# sr_indicator_v0_revA.net
KiCad netlist of a schematic drawn in EAGLE
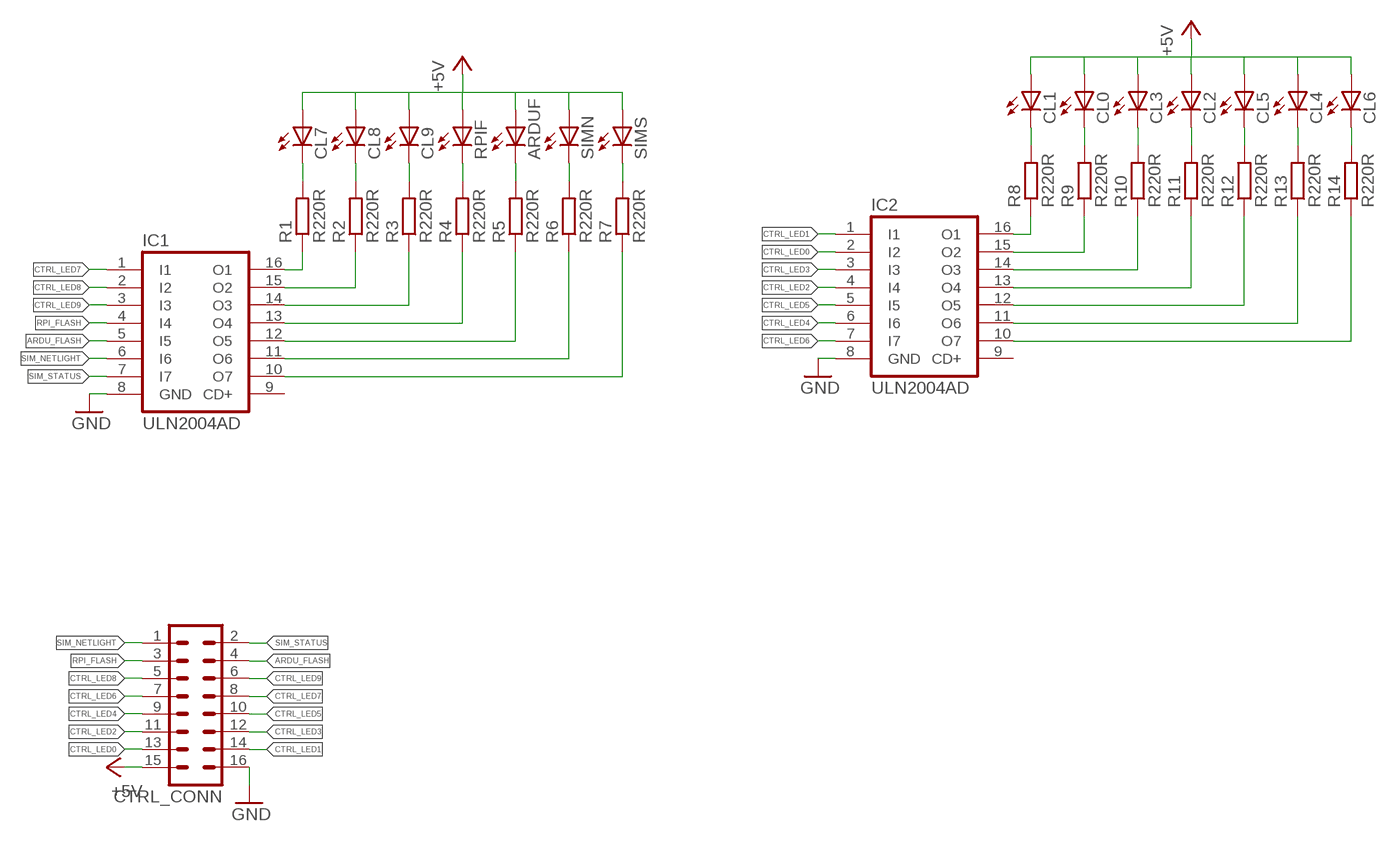
[diagram p0: schematic, sheet 1]

(export (version "E")
  (design (tool "Eeschema 10.0.6"))
  (components
    (comp (ref "ARDUF")
      (value "LED3MM")
      (footprint "eagle-import:LED3MM")
      (libsource (lib "eagle-import") (part "LED3MM"))
    )
    (comp (ref "CL0")
      (value "LED3MM")
      (footprint "eagle-import:LED3MM")
      (libsource (lib "eagle-import") (part "LED3MM"))
    )
    (comp (ref "CL1")
      (value "LED3MM")
      (footprint "eagle-import:LED3MM")
      (libsource (lib "eagle-import") (part "LED3MM"))
    )
    (comp (ref "CL2")
      (value "LED3MM")
      (footprint "eagle-import:LED3MM")
      (libsource (lib "eagle-import") (part "LED3MM"))
    )
    (comp (ref "CL3")
      (value "LED3MM")
      (footprint "eagle-import:LED3MM")
      (libsource (lib "eagle-import") (part "LED3MM"))
    )
    (comp (ref "CL4")
      (value "LED3MM")
      (footprint "eagle-import:LED3MM")
      (libsource (lib "eagle-import") (part "LED3MM"))
    )
    (comp (ref "CL5")
      (value "LED3MM")
      (footprint "eagle-import:LED3MM")
      (libsource (lib "eagle-import") (part "LED3MM"))
    )
    (comp (ref "CL6")
      (value "LED3MM")
      (footprint "eagle-import:LED3MM")
      (libsource (lib "eagle-import") (part "LED3MM"))
    )
    (comp (ref "CL7")
      (value "LED3MM")
      (footprint "eagle-import:LED3MM")
      (libsource (lib "eagle-import") (part "LED3MM"))
    )
    (comp (ref "CL8")
      (value "LED3MM")
      (footprint "eagle-import:LED3MM")
      (libsource (lib "eagle-import") (part "LED3MM"))
    )
    (comp (ref "CL9")
      (value "LED3MM")
      (footprint "eagle-import:LED3MM")
      (libsource (lib "eagle-import") (part "LED3MM"))
    )
    (comp (ref "CTRL_CONN")
      (value "MA08-2")
      (footprint "eagle-import:MA08-2")
      (libsource (lib "eagle-import") (part "MA08-2"))
    )
    (comp (ref "IC1")
      (value "ULN2004AD")
      (footprint "eagle-import:SO16")
      (libsource (lib "eagle-import") (part "ULN2004AD"))
    )
    (comp (ref "IC2")
      (value "ULN2004AD")
      (footprint "eagle-import:SO16")
      (libsource (lib "eagle-import") (part "ULN2004AD"))
    )
    (comp (ref "R1")
      (value "R220R")
      (footprint "eagle-import:M0805")
      (libsource (lib "eagle-import") (part "R-EU_M0805"))
    )
    (comp (ref "R2")
      (value "R220R")
      (footprint "eagle-import:M0805")
      (libsource (lib "eagle-import") (part "R-EU_M0805"))
    )
    (comp (ref "R3")
      (value "R220R")
      (footprint "eagle-import:M0805")
      (libsource (lib "eagle-import") (part "R-EU_M0805"))
    )
    (comp (ref "R4")
      (value "R220R")
      (footprint "eagle-import:M0805")
      (libsource (lib "eagle-import") (part "R-EU_M0805"))
    )
    (comp (ref "R5")
      (value "R220R")
      (footprint "eagle-import:M0805")
      (libsource (lib "eagle-import") (part "R-EU_M0805"))
    )
    (comp (ref "R6")
      (value "R220R")
      (footprint "eagle-import:M0805")
      (libsource (lib "eagle-import") (part "R-EU_M0805"))
    )
    (comp (ref "R7")
      (value "R220R")
      (footprint "eagle-import:M0805")
      (libsource (lib "eagle-import") (part "R-EU_M0805"))
    )
    (comp (ref "R8")
      (value "R220R")
      (footprint "eagle-import:M0805")
      (libsource (lib "eagle-import") (part "R-EU_M0805"))
    )
    (comp (ref "R9")
      (value "R220R")
      (footprint "eagle-import:M0805")
      (libsource (lib "eagle-import") (part "R-EU_M0805"))
    )
    (comp (ref "R10")
      (value "R220R")
      (footprint "eagle-import:M0805")
      (libsource (lib "eagle-import") (part "R-EU_M0805"))
    )
    (comp (ref "R11")
      (value "R220R")
      (footprint "eagle-import:M0805")
      (libsource (lib "eagle-import") (part "R-EU_M0805"))
    )
    (comp (ref "R12")
      (value "R220R")
      (footprint "eagle-import:M0805")
      (libsource (lib "eagle-import") (part "R-EU_M0805"))
    )
    (comp (ref "R13")
      (value "R220R")
      (footprint "eagle-import:M0805")
      (libsource (lib "eagle-import") (part "R-EU_M0805"))
    )
    (comp (ref "R14")
      (value "R220R")
      (footprint "eagle-import:M0805")
      (libsource (lib "eagle-import") (part "R-EU_M0805"))
    )
    (comp (ref "RPIF")
      (value "LED3MM")
      (footprint "eagle-import:LED3MM")
      (libsource (lib "eagle-import") (part "LED3MM"))
    )
    (comp (ref "SIMN")
      (value "LED3MM")
      (footprint "eagle-import:LED3MM")
      (libsource (lib "eagle-import") (part "LED3MM"))
    )
    (comp (ref "SIMS")
      (value "LED3MM")
      (footprint "eagle-import:LED3MM")
      (libsource (lib "eagle-import") (part "LED3MM"))
    )
  )
  (nets
    (net (code "1") (name "+5V") (class "Default")
      (node (ref "ARDUF") (pin "A") (pinfunction "A_A") (pintype "passive"))
      (node (ref "CL0") (pin "A") (pinfunction "A_A") (pintype "passive"))
      (node (ref "CL1") (pin "A") (pinfunction "A_A") (pintype "passive"))
      (node (ref "CL2") (pin "A") (pinfunction "A_A") (pintype "passive"))
      (node (ref "CL3") (pin "A") (pinfunction "A_A") (pintype "passive"))
      (node (ref "CL4") (pin "A") (pinfunction "A_A") (pintype "passive"))
      (node (ref "CL5") (pin "A") (pinfunction "A_A") (pintype "passive"))
      (node (ref "CL6") (pin "A") (pinfunction "A_A") (pintype "passive"))
      (node (ref "CL7") (pin "A") (pinfunction "A_A") (pintype "passive"))
      (node (ref "CL8") (pin "A") (pinfunction "A_A") (pintype "passive"))
      (node (ref "CL9") (pin "A") (pinfunction "A_A") (pintype "passive"))
      (node (ref "CTRL_CONN") (pin "15") (pinfunction "15_15") (pintype "passive"))
      (node (ref "RPIF") (pin "A") (pinfunction "A_A") (pintype "passive"))
      (node (ref "SIMN") (pin "A") (pinfunction "A_A") (pintype "passive"))
      (node (ref "SIMS") (pin "A") (pinfunction "A_A") (pintype "passive"))
    )
    (net (code "2") (name "ARDU_FLASH") (class "Default")
      (node (ref "CTRL_CONN") (pin "4") (pinfunction "4_4") (pintype "passive"))
      (node (ref "IC1") (pin "5") (pinfunction "I5_5") (pintype "input"))
    )
    (net (code "3") (name "CTRL_LED0") (class "Default")
      (node (ref "CTRL_CONN") (pin "13") (pinfunction "13_13") (pintype "passive"))
      (node (ref "IC2") (pin "2") (pinfunction "I2_2") (pintype "input"))
    )
    (net (code "4") (name "CTRL_LED1") (class "Default")
      (node (ref "CTRL_CONN") (pin "14") (pinfunction "14_14") (pintype "passive"))
      (node (ref "IC2") (pin "1") (pinfunction "I1_1") (pintype "input"))
    )
    (net (code "5") (name "CTRL_LED2") (class "Default")
      (node (ref "CTRL_CONN") (pin "11") (pinfunction "11_11") (pintype "passive"))
      (node (ref "IC2") (pin "4") (pinfunction "I4_4") (pintype "input"))
    )
    (net (code "6") (name "CTRL_LED3") (class "Default")
      (node (ref "CTRL_CONN") (pin "12") (pinfunction "12_12") (pintype "passive"))
      (node (ref "IC2") (pin "3") (pinfunction "I3_3") (pintype "input"))
    )
    (net (code "7") (name "CTRL_LED4") (class "Default")
      (node (ref "CTRL_CONN") (pin "9") (pinfunction "9_9") (pintype "passive"))
      (node (ref "IC2") (pin "6") (pinfunction "I6_6") (pintype "input"))
    )
    (net (code "8") (name "CTRL_LED5") (class "Default")
      (node (ref "CTRL_CONN") (pin "10") (pinfunction "10_10") (pintype "passive"))
      (node (ref "IC2") (pin "5") (pinfunction "I5_5") (pintype "input"))
    )
    (net (code "9") (name "CTRL_LED6") (class "Default")
      (node (ref "CTRL_CONN") (pin "7") (pinfunction "7_7") (pintype "passive"))
      (node (ref "IC2") (pin "7") (pinfunction "I7_7") (pintype "input"))
    )
    (net (code "10") (name "CTRL_LED7") (class "Default")
      (node (ref "CTRL_CONN") (pin "8") (pinfunction "8_8") (pintype "passive"))
      (node (ref "IC1") (pin "1") (pinfunction "I1_1") (pintype "input"))
    )
    (net (code "11") (name "CTRL_LED8") (class "Default")
      (node (ref "CTRL_CONN") (pin "5") (pinfunction "5_5") (pintype "passive"))
      (node (ref "IC1") (pin "2") (pinfunction "I2_2") (pintype "input"))
    )
    (net (code "12") (name "CTRL_LED9") (class "Default")
      (node (ref "CTRL_CONN") (pin "6") (pinfunction "6_6") (pintype "passive"))
      (node (ref "IC1") (pin "3") (pinfunction "I3_3") (pintype "input"))
    )
    (net (code "13") (name "GND") (class "Default")
      (node (ref "CTRL_CONN") (pin "16") (pinfunction "16_16") (pintype "passive"))
      (node (ref "IC1") (pin "8") (pinfunction "GND_8") (pintype "power_in"))
      (node (ref "IC2") (pin "8") (pinfunction "GND_8") (pintype "power_in"))
    )
    (net (code "14") (name "Net-(ARDUF-C)") (class "Default")
      (node (ref "ARDUF") (pin "K") (pinfunction "C_K") (pintype "passive"))
      (node (ref "R5") (pin "2") (pinfunction "2_2") (pintype "passive"))
    )
    (net (code "15") (name "Net-(CL0-C)") (class "Default")
      (node (ref "CL0") (pin "K") (pinfunction "C_K") (pintype "passive"))
      (node (ref "R9") (pin "2") (pinfunction "2_2") (pintype "passive"))
    )
    (net (code "16") (name "Net-(CL1-C)") (class "Default")
      (node (ref "CL1") (pin "K") (pinfunction "C_K") (pintype "passive"))
      (node (ref "R8") (pin "2") (pinfunction "2_2") (pintype "passive"))
    )
    (net (code "17") (name "Net-(CL2-C)") (class "Default")
      (node (ref "CL2") (pin "K") (pinfunction "C_K") (pintype "passive"))
      (node (ref "R11") (pin "2") (pinfunction "2_2") (pintype "passive"))
    )
    (net (code "18") (name "Net-(CL3-C)") (class "Default")
      (node (ref "CL3") (pin "K") (pinfunction "C_K") (pintype "passive"))
      (node (ref "R10") (pin "2") (pinfunction "2_2") (pintype "passive"))
    )
    (net (code "19") (name "Net-(CL4-C)") (class "Default")
      (node (ref "CL4") (pin "K") (pinfunction "C_K") (pintype "passive"))
      (node (ref "R13") (pin "2") (pinfunction "2_2") (pintype "passive"))
    )
    (net (code "20") (name "Net-(CL5-C)") (class "Default")
      (node (ref "CL5") (pin "K") (pinfunction "C_K") (pintype "passive"))
      (node (ref "R12") (pin "2") (pinfunction "2_2") (pintype "passive"))
    )
    (net (code "21") (name "Net-(CL6-C)") (class "Default")
      (node (ref "CL6") (pin "K") (pinfunction "C_K") (pintype "passive"))
      (node (ref "R14") (pin "2") (pinfunction "2_2") (pintype "passive"))
    )
    (net (code "22") (name "Net-(CL7-C)") (class "Default")
      (node (ref "CL7") (pin "K") (pinfunction "C_K") (pintype "passive"))
      (node (ref "R1") (pin "2") (pinfunction "2_2") (pintype "passive"))
    )
    (net (code "23") (name "Net-(CL8-C)") (class "Default")
      (node (ref "CL8") (pin "K") (pinfunction "C_K") (pintype "passive"))
      (node (ref "R2") (pin "2") (pinfunction "2_2") (pintype "passive"))
    )
    (net (code "24") (name "Net-(CL9-C)") (class "Default")
      (node (ref "CL9") (pin "K") (pinfunction "C_K") (pintype "passive"))
      (node (ref "R3") (pin "2") (pinfunction "2_2") (pintype "passive"))
    )
    (net (code "25") (name "Net-(IC1-O1)") (class "Default")
      (node (ref "IC1") (pin "16") (pinfunction "O1_16") (pintype "open_collector"))
      (node (ref "R1") (pin "1") (pinfunction "1_1") (pintype "passive"))
    )
    (net (code "26") (name "Net-(IC1-O2)") (class "Default")
      (node (ref "IC1") (pin "15") (pinfunction "O2_15") (pintype "open_collector"))
      (node (ref "R2") (pin "1") (pinfunction "1_1") (pintype "passive"))
    )
    (net (code "27") (name "Net-(IC1-O3)") (class "Default")
      (node (ref "IC1") (pin "14") (pinfunction "O3_14") (pintype "open_collector"))
      (node (ref "R3") (pin "1") (pinfunction "1_1") (pintype "passive"))
    )
    (net (code "28") (name "Net-(IC1-O4)") (class "Default")
      (node (ref "IC1") (pin "13") (pinfunction "O4_13") (pintype "open_collector"))
      (node (ref "R4") (pin "1") (pinfunction "1_1") (pintype "passive"))
    )
    (net (code "29") (name "Net-(IC1-O5)") (class "Default")
      (node (ref "IC1") (pin "12") (pinfunction "O5_12") (pintype "open_collector"))
      (node (ref "R5") (pin "1") (pinfunction "1_1") (pintype "passive"))
    )
    (net (code "30") (name "Net-(IC1-O6)") (class "Default")
      (node (ref "IC1") (pin "11") (pinfunction "O6_11") (pintype "open_collector"))
      (node (ref "R6") (pin "1") (pinfunction "1_1") (pintype "passive"))
    )
    (net (code "31") (name "Net-(IC1-O7)") (class "Default")
      (node (ref "IC1") (pin "10") (pinfunction "O7_10") (pintype "open_collector"))
      (node (ref "R7") (pin "1") (pinfunction "1_1") (pintype "passive"))
    )
    (net (code "32") (name "Net-(IC2-O1)") (class "Default")
      (node (ref "IC2") (pin "16") (pinfunction "O1_16") (pintype "open_collector"))
      (node (ref "R8") (pin "1") (pinfunction "1_1") (pintype "passive"))
    )
    (net (code "33") (name "Net-(IC2-O2)") (class "Default")
      (node (ref "IC2") (pin "15") (pinfunction "O2_15") (pintype "open_collector"))
      (node (ref "R9") (pin "1") (pinfunction "1_1") (pintype "passive"))
    )
    (net (code "34") (name "Net-(IC2-O3)") (class "Default")
      (node (ref "IC2") (pin "14") (pinfunction "O3_14") (pintype "open_collector"))
      (node (ref "R10") (pin "1") (pinfunction "1_1") (pintype "passive"))
    )
    (net (code "35") (name "Net-(IC2-O4)") (class "Default")
      (node (ref "IC2") (pin "13") (pinfunction "O4_13") (pintype "open_collector"))
      (node (ref "R11") (pin "1") (pinfunction "1_1") (pintype "passive"))
    )
    (net (code "36") (name "Net-(IC2-O5)") (class "Default")
      (node (ref "IC2") (pin "12") (pinfunction "O5_12") (pintype "open_collector"))
      (node (ref "R12") (pin "1") (pinfunction "1_1") (pintype "passive"))
    )
    (net (code "37") (name "Net-(IC2-O6)") (class "Default")
      (node (ref "IC2") (pin "11") (pinfunction "O6_11") (pintype "open_collector"))
      (node (ref "R13") (pin "1") (pinfunction "1_1") (pintype "passive"))
    )
    (net (code "38") (name "Net-(IC2-O7)") (class "Default")
      (node (ref "IC2") (pin "10") (pinfunction "O7_10") (pintype "open_collector"))
      (node (ref "R14") (pin "1") (pinfunction "1_1") (pintype "passive"))
    )
    (net (code "39") (name "Net-(RPIF-C)") (class "Default")
      (node (ref "R4") (pin "2") (pinfunction "2_2") (pintype "passive"))
      (node (ref "RPIF") (pin "K") (pinfunction "C_K") (pintype "passive"))
    )
    (net (code "40") (name "Net-(SIMN-C)") (class "Default")
      (node (ref "R6") (pin "2") (pinfunction "2_2") (pintype "passive"))
      (node (ref "SIMN") (pin "K") (pinfunction "C_K") (pintype "passive"))
    )
    (net (code "41") (name "Net-(SIMS-C)") (class "Default")
      (node (ref "R7") (pin "2") (pinfunction "2_2") (pintype "passive"))
      (node (ref "SIMS") (pin "K") (pinfunction "C_K") (pintype "passive"))
    )
    (net (code "42") (name "RPI_FLASH") (class "Default")
      (node (ref "CTRL_CONN") (pin "3") (pinfunction "3_3") (pintype "passive"))
      (node (ref "IC1") (pin "4") (pinfunction "I4_4") (pintype "input"))
    )
    (net (code "43") (name "SIM_NETLIGHT") (class "Default")
      (node (ref "CTRL_CONN") (pin "1") (pinfunction "1_1") (pintype "passive"))
      (node (ref "IC1") (pin "6") (pinfunction "I6_6") (pintype "input"))
    )
    (net (code "44") (name "SIM_STATUS") (class "Default")
      (node (ref "CTRL_CONN") (pin "2") (pinfunction "2_2") (pintype "passive"))
      (node (ref "IC1") (pin "7") (pinfunction "I7_7") (pintype "input"))
    )
    (net (code "45") (name "unconnected-(IC1-CD+-Pad9)") (class "Default")
      (node (ref "IC1") (pin "9") (pinfunction "CD+_9") (pintype "passive"))
    )
    (net (code "46") (name "unconnected-(IC2-CD+-Pad9)") (class "Default")
      (node (ref "IC2") (pin "9") (pinfunction "CD+_9") (pintype "passive"))
    )
  )
)
